# 1XGSH00_LCD.net
KiCad netlist of a schematic drawn in Altium Designer
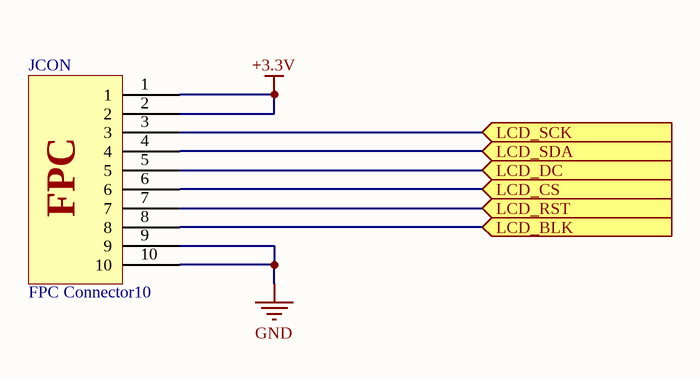
[diagram p0: 1XGSH00_LCD.SchDoc]

(export (version "E")
  (design (tool "Eeschema 10.0.6"))
  (components
    (comp (ref "JCON")
      (value "FPC Connector10")
      (footprint "FPC-SMD_10P")
      (description "FPC 0.5mm 14P")
      (libsource (lib "LGG21") (part "FPC Connector10"))
    )
  )
  (nets
    (net (code "1") (name "+3.3V") (class "Default")
      (node (ref "JCON") (pin "1") (pinfunction "1_1") (pintype "passive"))
      (node (ref "JCON") (pin "2") (pinfunction "2_2") (pintype "passive"))
    )
    (net (code "2") (name "/LCD_BLK") (class "Default")
      (node (ref "JCON") (pin "8") (pinfunction "8_8") (pintype "passive"))
    )
    (net (code "3") (name "/LCD_CS") (class "Default")
      (node (ref "JCON") (pin "6") (pinfunction "6_6") (pintype "passive"))
    )
    (net (code "4") (name "/LCD_DC") (class "Default")
      (node (ref "JCON") (pin "5") (pinfunction "5_5") (pintype "passive"))
    )
    (net (code "5") (name "/LCD_RST") (class "Default")
      (node (ref "JCON") (pin "7") (pinfunction "7_7") (pintype "passive"))
    )
    (net (code "6") (name "/LCD_SCK") (class "Default")
      (node (ref "JCON") (pin "3") (pinfunction "3_3") (pintype "passive"))
    )
    (net (code "7") (name "/LCD_SDA") (class "Default")
      (node (ref "JCON") (pin "4") (pinfunction "4_4") (pintype "passive"))
    )
    (net (code "8") (name "GND") (class "Default")
      (node (ref "JCON") (pin "10") (pinfunction "10_10") (pintype "passive"))
      (node (ref "JCON") (pin "9") (pinfunction "9_9") (pintype "passive"))
    )
  )
)
